# SparkFun_XBee3_Cat1_Smart_Modem.net
KiCad netlist of a schematic drawn in EAGLE
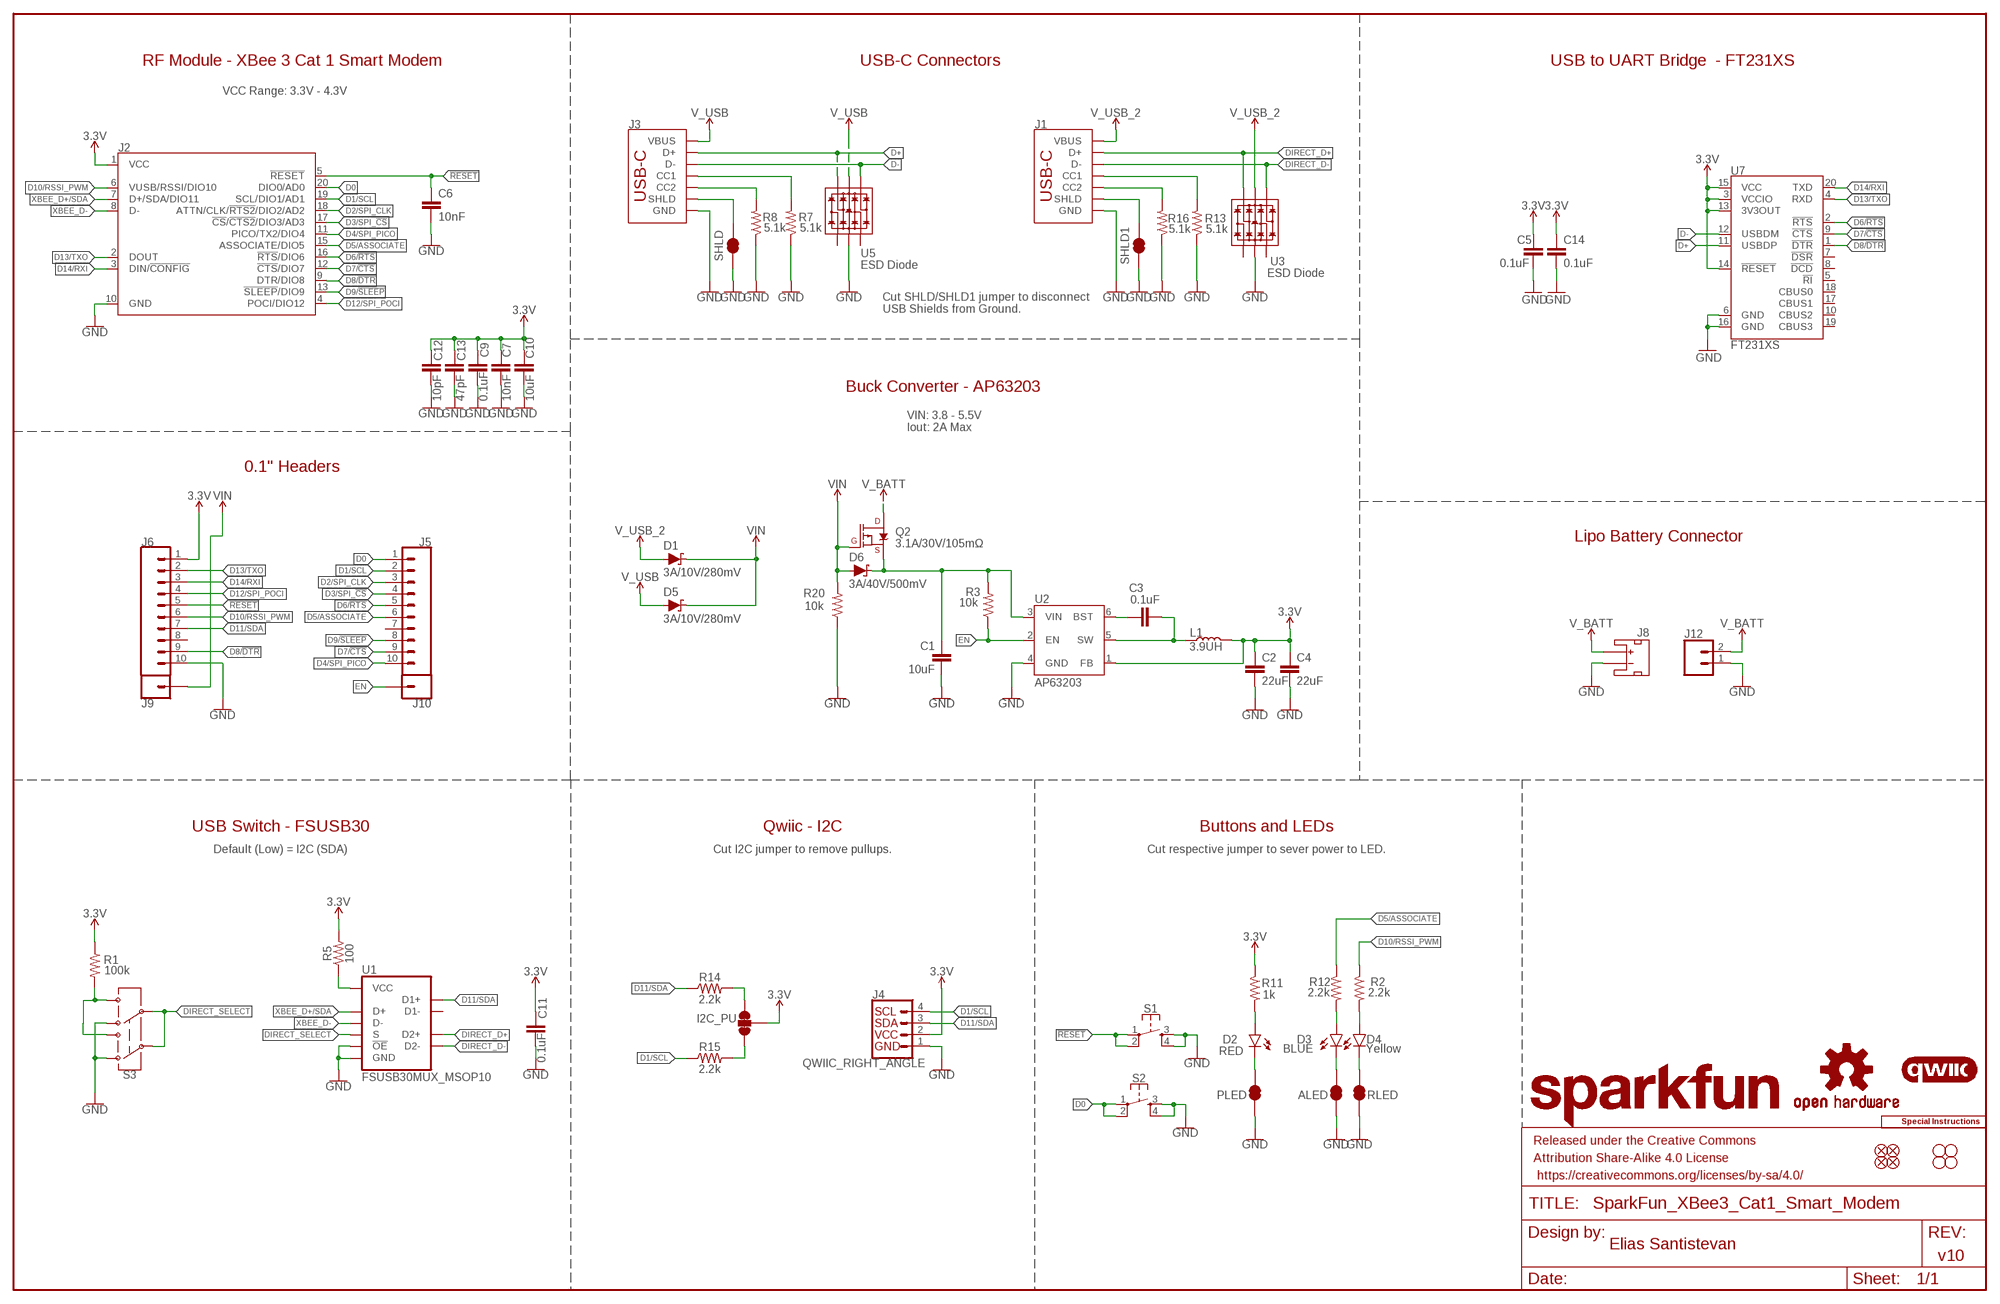
[diagram p0: schematic, sheet 1]

(export (version "E")
  (design (tool "Eeschema 10.0.6"))
  (components
    (comp (ref "ALED")
      (value "JUMPER-SMT_2_NC_TRACE_SILK")
      (footprint "eagle-import:SMT-JUMPER_2_NC_TRACE_SILK")
      (libsource (lib "eagle-import") (part "JUMPER-SMT_2_NC_TRACE_SILK"))
    )
    (comp (ref "C1")
      (value "10uF")
      (footprint "eagle-import:1210")
      (libsource (lib "eagle-import") (part "10UF-1210-50V-20%"))
    )
    (comp (ref "C2")
      (value "22uF")
      (footprint "eagle-import:0603")
      (libsource (lib "eagle-import") (part "22UF-0603-6.3V-20%"))
    )
    (comp (ref "C3")
      (value "0.1uF")
      (footprint "eagle-import:0603")
      (libsource (lib "eagle-import") (part "0.1UF-0603-25V-5%"))
    )
    (comp (ref "C4")
      (value "22uF")
      (footprint "eagle-import:0603")
      (libsource (lib "eagle-import") (part "22UF-0603-6.3V-20%"))
    )
    (comp (ref "C5")
      (value "0.1uF")
      (footprint "eagle-import:0603")
      (libsource (lib "eagle-import") (part "0.1UF-0603-25V-(+80/-20%)"))
    )
    (comp (ref "C6")
      (value "10nF")
      (footprint "eagle-import:0603")
      (libsource (lib "eagle-import") (part "10NF-0603-50V-10%"))
    )
    (comp (ref "C7")
      (value "10nF")
      (footprint "eagle-import:0603")
      (libsource (lib "eagle-import") (part "10NF-0603-50V-10%"))
    )
    (comp (ref "C9")
      (value "0.1uF")
      (footprint "eagle-import:0603")
      (libsource (lib "eagle-import") (part "0.1UF-0603-25V-(+80/-20%)"))
    )
    (comp (ref "C10")
      (value "10uF")
      (footprint "eagle-import:0603")
      (libsource (lib "eagle-import") (part "10UF-0603-6.3V-20%"))
    )
    (comp (ref "C11")
      (value "0.1uF")
      (footprint "eagle-import:0603")
      (libsource (lib "eagle-import") (part "0.1UF-0603-25V-(+80/-20%)"))
    )
    (comp (ref "C12")
      (value "10pF")
      (footprint "eagle-import:0603")
      (libsource (lib "eagle-import") (part "10PF-0603-50V-5%"))
    )
    (comp (ref "C13")
      (value "47pF")
      (footprint "eagle-import:0603")
      (libsource (lib "eagle-import") (part "47PF-0603-50V-5%"))
    )
    (comp (ref "C14")
      (value "0.1uF")
      (footprint "eagle-import:0603")
      (libsource (lib "eagle-import") (part "0.1UF-0603-25V-(+80/-20%)"))
    )
    (comp (ref "D1")
      (value "3A/10V/280mV")
      (footprint "eagle-import:SOD-323")
      (libsource (lib "eagle-import") (part "DIODE-SCHOTTKY-BAT60A"))
    )
    (comp (ref "D2")
      (value "RED")
      (footprint "eagle-import:LED-0603")
      (libsource (lib "eagle-import") (part "LED-RED0603"))
    )
    (comp (ref "D3")
      (value "BLUE")
      (footprint "eagle-import:LED-0603")
      (libsource (lib "eagle-import") (part "LED-BLUE0603"))
    )
    (comp (ref "D4")
      (value "Yellow")
      (footprint "eagle-import:LED-0603")
      (libsource (lib "eagle-import") (part "LED-YELLOW0603"))
    )
    (comp (ref "D5")
      (value "3A/10V/280mV")
      (footprint "eagle-import:SOD-323")
      (libsource (lib "eagle-import") (part "DIODE-SCHOTTKY-BAT60A"))
    )
    (comp (ref "D6")
      (value "3A/40V/500mV")
      (footprint "eagle-import:SMA-DIODE")
      (libsource (lib "eagle-import") (part "DIODE-SCHOTTKY-B340A"))
    )
    (comp (ref "FD1")
      (value "FIDUCIAL1X2")
      (footprint "eagle-import:FIDUCIAL-1X2")
      (libsource (lib "eagle-import") (part "FIDUCIAL1X2"))
    )
    (comp (ref "FD2")
      (value "FIDUCIAL1X2")
      (footprint "eagle-import:FIDUCIAL-1X2")
      (libsource (lib "eagle-import") (part "FIDUCIAL1X2"))
    )
    (comp (ref "FD3")
      (value "FIDUCIAL1X2")
      (footprint "eagle-import:FIDUCIAL-1X2")
      (libsource (lib "eagle-import") (part "FIDUCIAL1X2"))
    )
    (comp (ref "FD4")
      (value "FIDUCIAL1X2")
      (footprint "eagle-import:FIDUCIAL-1X2")
      (libsource (lib "eagle-import") (part "FIDUCIAL1X2"))
    )
    (comp (ref "FRAME1")
      (value "FRAME-LEDGER")
      (footprint "eagle-import:CREATIVE_COMMONS")
      (libsource (lib "eagle-import") (part "FRAME-LEDGER"))
    )
    (comp (ref "H1")
      (value "STAND-OFFTIGHT")
      (footprint "eagle-import:STAND-OFF-TIGHT")
      (libsource (lib "eagle-import") (part "STAND-OFFTIGHT"))
    )
    (comp (ref "H2")
      (value "STAND-OFFTIGHT")
      (footprint "eagle-import:STAND-OFF-TIGHT")
      (libsource (lib "eagle-import") (part "STAND-OFFTIGHT"))
    )
    (comp (ref "H3")
      (value "STAND-OFFTIGHT")
      (footprint "eagle-import:STAND-OFF-TIGHT")
      (libsource (lib "eagle-import") (part "STAND-OFFTIGHT"))
    )
    (comp (ref "H4")
      (value "STAND-OFFTIGHT")
      (footprint "eagle-import:STAND-OFF-TIGHT")
      (libsource (lib "eagle-import") (part "STAND-OFFTIGHT"))
    )
    (comp (ref "I2C_PU")
      (value "JUMPER-SMT_3_2-NC_TRACE_SILK")
      (footprint "eagle-import:SMT-JUMPER_3_2-NC_TRACE_SILK")
      (libsource (lib "eagle-import") (part "JUMPER-SMT_3_2-NC_TRACE_SILK"))
    )
    (comp (ref "J1")
      (value "USB Female Type C Connector")
      (footprint "eagle-import:USB-C-16P-4LAYER-ISOLATED")
      (libsource (lib "eagle-import") (part "USB_C_4-LAYER-ISOLATED"))
    )
    (comp (ref "J2")
      (value "XBEE_UPDATEXBEE_SMD")
      (footprint "eagle-import:XBEE3-SMD")
      (libsource (lib "eagle-import") (part "XBEE_UPDATEXBEE_SMD"))
    )
    (comp (ref "J3")
      (value "USB Female Type C Connector")
      (footprint "eagle-import:USB-C-16P-4LAYER-ISOLATED")
      (libsource (lib "eagle-import") (part "USB_C_4-LAYER-ISOLATED"))
    )
    (comp (ref "J4")
      (value "QWIIC_RIGHT_ANGLE")
      (footprint "eagle-import:JST04_1MM_RA")
      (libsource (lib "eagle-import") (part "QWIIC_CONNECTORJS-1MM"))
    )
    (comp (ref "J5")
      (value "CONN_10NO_SILK_PTH_FEMALE")
      (footprint "eagle-import:1X10_NO_SILK")
      (libsource (lib "eagle-import") (part "CONN_10NO_SILK_PTH_FEMALE"))
    )
    (comp (ref "J6")
      (value "CONN_10NO_SILK_PTH_FEMALE")
      (footprint "eagle-import:1X10_NO_SILK")
      (libsource (lib "eagle-import") (part "CONN_10NO_SILK_PTH_FEMALE"))
    )
    (comp (ref "J8")
      (value "JST_2MM_MALE")
      (footprint "eagle-import:JST-2-SMD")
      (libsource (lib "eagle-import") (part "JST_2MM_MALE"))
    )
    (comp (ref "J9")
      (value "CONN_01PTH_NO_SILK_STAND")
      (footprint "eagle-import:1X01_NO_SILK_STAND")
      (libsource (lib "eagle-import") (part "CONN_01PTH_NO_SILK_STAND"))
    )
    (comp (ref "J10")
      (value "CONN_01PTH_NO_SILK_STAND")
      (footprint "eagle-import:1X01_NO_SILK_STAND")
      (libsource (lib "eagle-import") (part "CONN_01PTH_NO_SILK_STAND"))
    )
    (comp (ref "J12")
      (value "CONN_021X02_NO_SILK")
      (footprint "eagle-import:1X02_NO_SILK")
      (libsource (lib "eagle-import") (part "CONN_021X02_NO_SILK"))
    )
    (comp (ref "L1")
      (value "3.9UH")
      (footprint "eagle-import:INDUCTOR_3.9UH")
      (libsource (lib "eagle-import") (part "3.9UH"))
    )
    (comp (ref "LOGO1")
      (value "SFE_LOGO_NAME.2_INCH")
      (footprint "eagle-import:SFE_LOGO_NAME_.2")
      (libsource (lib "eagle-import") (part "SFE_LOGO_NAME.2_INCH"))
    )
    (comp (ref "LOGO2")
      (value "OSHW-LOGOS")
      (footprint "eagle-import:OSHW-LOGO-S")
      (libsource (lib "eagle-import") (part "OSHW-LOGOS"))
    )
    (comp (ref "LOGO3")
      (value "QWIIC_LOGO_5MM")
      (footprint "eagle-import:QWIIC_5MM")
      (libsource (lib "eagle-import") (part "QWIIC_LOGO_5MM"))
    )
    (comp (ref "LOGO5")
      (value "SPECIAL_INSTRUCTIONS-ORDERING")
      (footprint "eagle-import:ORDERING_INSTRUCTIONS")
      (libsource (lib "eagle-import") (part "SPECIAL_INSTRUCTIONS-ORDERING"))
    )
    (comp (ref "PLED")
      (value "JUMPER-SMT_2_NC_TRACE_SILK")
      (footprint "eagle-import:SMT-JUMPER_2_NC_TRACE_SILK")
      (libsource (lib "eagle-import") (part "JUMPER-SMT_2_NC_TRACE_SILK"))
    )
    (comp (ref "Q2")
      (value "3.1A/30V/105mΩ")
      (footprint "eagle-import:SOT23-3")
      (libsource (lib "eagle-import") (part "MOSFET_PCH-DMG2307L"))
    )
    (comp (ref "R1")
      (value "100k")
      (footprint "eagle-import:0603")
      (libsource (lib "eagle-import") (part "100KOHM-0603-1/10W-1%"))
    )
    (comp (ref "R2")
      (value "2.2k")
      (footprint "eagle-import:0603")
      (libsource (lib "eagle-import") (part "2.2KOHM-0603-1/10W-1%"))
    )
    (comp (ref "R3")
      (value "10k")
      (footprint "eagle-import:0603")
      (libsource (lib "eagle-import") (part "10KOHM-0603-1/10W-1%"))
    )
    (comp (ref "R5")
      (value "100")
      (footprint "eagle-import:0603")
      (libsource (lib "eagle-import") (part "100OHM-0603-1/10W-1%"))
    )
    (comp (ref "R7")
      (value "5.1k")
      (footprint "eagle-import:0603")
      (libsource (lib "eagle-import") (part "5.1KOHM5.1KOHM-0603-1/10W-1%"))
    )
    (comp (ref "R8")
      (value "5.1k")
      (footprint "eagle-import:0603")
      (libsource (lib "eagle-import") (part "5.1KOHM5.1KOHM-0603-1/10W-1%"))
    )
    (comp (ref "R11")
      (value "1k")
      (footprint "eagle-import:0603")
      (libsource (lib "eagle-import") (part "1KOHM-0603-1/10W-1%"))
    )
    (comp (ref "R12")
      (value "2.2k")
      (footprint "eagle-import:0603")
      (libsource (lib "eagle-import") (part "2.2KOHM-0603-1/10W-1%"))
    )
    (comp (ref "R13")
      (value "5.1k")
      (footprint "eagle-import:0603")
      (libsource (lib "eagle-import") (part "5.1KOHM5.1KOHM-0603-1/10W-1%"))
    )
    (comp (ref "R14")
      (value "2.2k")
      (footprint "eagle-import:0603")
      (libsource (lib "eagle-import") (part "2.2KOHM-0603-1/10W-1%"))
    )
    (comp (ref "R15")
      (value "2.2k")
      (footprint "eagle-import:0603")
      (libsource (lib "eagle-import") (part "2.2KOHM-0603-1/10W-1%"))
    )
    (comp (ref "R16")
      (value "5.1k")
      (footprint "eagle-import:0603")
      (libsource (lib "eagle-import") (part "5.1KOHM5.1KOHM-0603-1/10W-1%"))
    )
    (comp (ref "R20")
      (value "10k")
      (footprint "eagle-import:0603")
      (libsource (lib "eagle-import") (part "10KOHM-0603-1/10W-1%"))
    )
    (comp (ref "RLED")
      (value "JUMPER-SMT_2_NC_TRACE_SILK")
      (footprint "eagle-import:SMT-JUMPER_2_NC_TRACE_SILK")
      (libsource (lib "eagle-import") (part "JUMPER-SMT_2_NC_TRACE_SILK"))
    )
    (comp (ref "S1")
      (value "MOMENTARY-SWITCH-SPST-2-SMD-5.2MM-TALL")
      (footprint "eagle-import:TACTILE_SWITCH_SMD_5.2MM")
      (libsource (lib "eagle-import") (part "MOMENTARY-SWITCH-SPST-2-SMD-5.2MM-TALL"))
    )
    (comp (ref "S2")
      (value "MOMENTARY-SWITCH-SPST-2-SMD-5.2MM-TALL")
      (footprint "eagle-import:TACTILE_SWITCH_SMD_5.2MM")
      (libsource (lib "eagle-import") (part "MOMENTARY-SWITCH-SPST-2-SMD-5.2MM-TALL"))
    )
    (comp (ref "S3")
      (value "SWITCH-DPDT-SMD-AYZ0202")
      (footprint "eagle-import:SWITCH_DPDT_SMD_AYZ0202")
      (libsource (lib "eagle-import") (part "SWITCH-DPDT-SMD-AYZ0202"))
    )
    (comp (ref "SHLD")
      (value "JUMPER-SMT_2_NC_TRACE_SILK")
      (footprint "eagle-import:SMT-JUMPER_2_NC_TRACE_SILK")
      (libsource (lib "eagle-import") (part "JUMPER-SMT_2_NC_TRACE_SILK"))
    )
    (comp (ref "SHLD1")
      (value "JUMPER-SMT_2_NC_TRACE_SILK")
      (footprint "eagle-import:SMT-JUMPER_2_NC_TRACE_SILK")
      (libsource (lib "eagle-import") (part "JUMPER-SMT_2_NC_TRACE_SILK"))
    )
    (comp (ref "U1")
      (value "FSUSB30MUX_MSOP10")
      (footprint "eagle-import:MSOP10")
      (libsource (lib "eagle-import") (part "FSUSB30MUX_MSOP10"))
    )
    (comp (ref "U2")
      (value "AP63203")
      (footprint "eagle-import:SOT23-6")
      (libsource (lib "eagle-import") (part "AP63203"))
    )
    (comp (ref "U3")
      (value "ESD Diode")
      (footprint "eagle-import:SOT-23-6")
      (libsource (lib "eagle-import") (part "TVS_DIODE_ARRAY_DT1042-04SO-7"))
    )
    (comp (ref "U5")
      (value "ESD Diode")
      (footprint "eagle-import:SOT-23-6")
      (libsource (lib "eagle-import") (part "TVS_DIODE_ARRAY_DT1042-04SO-7"))
    )
    (comp (ref "U7")
      (value "FT231XS")
      (footprint "eagle-import:SSOP20_L")
      (libsource (lib "eagle-import") (part "FT231XS"))
    )
  )
  (nets
    (net (code "1") (name "/D3{slash}SPI_~{CS}") (class "Default")
      (node (ref "J2") (pin "17") (pinfunction "~{CS}/~{CTS2}/DIO3/AD3_17") (pintype "bidirectional"))
      (node (ref "J5") (pin "4") (pinfunction "4_4") (pintype "passive"))
    )
    (net (code "2") (name "/D6{slash}~{RTS}") (class "Default")
      (node (ref "J2") (pin "16") (pinfunction "~{RTS}/DIO6_16") (pintype "input"))
      (node (ref "J5") (pin "5") (pinfunction "5_5") (pintype "passive"))
      (node (ref "U7") (pin "2") (pinfunction "~{RTS}_2") (pintype "bidirectional"))
    )
    (net (code "3") (name "/D7{slash}~{CTS}") (class "Default")
      (node (ref "J2") (pin "12") (pinfunction "~{CTS}/DIO7_12") (pintype "output"))
      (node (ref "J5") (pin "9") (pinfunction "9_9") (pintype "passive"))
      (node (ref "U7") (pin "9") (pinfunction "~{CTS}_9") (pintype "bidirectional"))
    )
    (net (code "4") (name "/D8{slash}~{DTR}") (class "Default")
      (node (ref "J2") (pin "9") (pinfunction "DTR/DIO8_9") (pintype "bidirectional"))
      (node (ref "J6") (pin "9") (pinfunction "9_9") (pintype "passive"))
      (node (ref "U7") (pin "1") (pinfunction "~{DTR}_1") (pintype "bidirectional"))
    )
    (net (code "5") (name "/D9{slash}~{SLEEP}") (class "Default")
      (node (ref "J2") (pin "13") (pinfunction "~{SLEEP}/DIO9_13") (pintype "bidirectional"))
      (node (ref "J5") (pin "8") (pinfunction "8_8") (pintype "passive"))
    )
    (net (code "6") (name "/~{RESET}") (class "Default")
      (node (ref "C6") (pin "1") (pinfunction "1_1") (pintype "passive"))
      (node (ref "J2") (pin "5") (pinfunction "~{RESET}_5") (pintype "input"))
      (node (ref "J6") (pin "5") (pinfunction "5_5") (pintype "passive"))
      (node (ref "S1") (pin "1") (pinfunction "1_1") (pintype "passive"))
      (node (ref "S1") (pin "2") (pinfunction "2_2") (pintype "passive"))
    )
    (net (code "7") (name "3.3V") (class "Default")
      (node (ref "C10") (pin "1") (pinfunction "1_1") (pintype "passive"))
      (node (ref "C11") (pin "1") (pinfunction "1_1") (pintype "passive"))
      (node (ref "C12") (pin "1") (pinfunction "1_1") (pintype "passive"))
      (node (ref "C13") (pin "1") (pinfunction "1_1") (pintype "passive"))
      (node (ref "C14") (pin "1") (pinfunction "1_1") (pintype "passive"))
      (node (ref "C2") (pin "1") (pinfunction "1_1") (pintype "passive"))
      (node (ref "C4") (pin "1") (pinfunction "1_1") (pintype "passive"))
      (node (ref "C5") (pin "1") (pinfunction "1_1") (pintype "passive"))
      (node (ref "C7") (pin "1") (pinfunction "1_1") (pintype "passive"))
      (node (ref "C9") (pin "1") (pinfunction "1_1") (pintype "passive"))
      (node (ref "I2C_PU") (pin "2") (pinfunction "2_2") (pintype "passive"))
      (node (ref "J2") (pin "1") (pinfunction "VCC_1") (pintype "power_in"))
      (node (ref "J4") (pin "2") (pinfunction "2_2") (pintype "power_in"))
      (node (ref "J6") (pin "1") (pinfunction "1_1") (pintype "passive"))
      (node (ref "L1") (pin "P$2") (pinfunction "2_P$2") (pintype "passive"))
      (node (ref "R1") (pin "1") (pinfunction "1_1") (pintype "passive"))
      (node (ref "R11") (pin "1") (pinfunction "1_1") (pintype "passive"))
      (node (ref "R5") (pin "2") (pinfunction "2_2") (pintype "passive"))
      (node (ref "U2") (pin "1") (pinfunction "FB_1") (pintype "bidirectional"))
      (node (ref "U7") (pin "13") (pinfunction "3V3OUT_13") (pintype "bidirectional"))
      (node (ref "U7") (pin "14") (pinfunction "~{RESET}_14") (pintype "bidirectional"))
      (node (ref "U7") (pin "15") (pinfunction "VCC_15") (pintype "bidirectional"))
      (node (ref "U7") (pin "3") (pinfunction "VCCIO_3") (pintype "bidirectional"))
    )
    (net (code "8") (name "D+") (class "Default")
      (node (ref "J3") (pin "A6") (pinfunction "D+_A6") (pintype "bidirectional"))
      (node (ref "J3") (pin "B6") (pinfunction "D+_B6") (pintype "bidirectional"))
      (node (ref "U5") (pin "6") (pinfunction "IO4_6") (pintype "bidirectional"))
      (node (ref "U7") (pin "11") (pinfunction "USBDP_11") (pintype "bidirectional"))
    )
    (net (code "9") (name "D-") (class "Default")
      (node (ref "J3") (pin "A7") (pinfunction "D-_A7") (pintype "bidirectional"))
      (node (ref "J3") (pin "B7") (pinfunction "D-_B7") (pintype "bidirectional"))
      (node (ref "U5") (pin "4") (pinfunction "IO3_4") (pintype "bidirectional"))
      (node (ref "U7") (pin "12") (pinfunction "USBDM_12") (pintype "bidirectional"))
    )
    (net (code "10") (name "D0") (class "Default")
      (node (ref "J2") (pin "20") (pinfunction "DIO0/AD0_20") (pintype "bidirectional"))
      (node (ref "J5") (pin "1") (pinfunction "1_1") (pintype "passive"))
      (node (ref "S2") (pin "1") (pinfunction "1_1") (pintype "passive"))
      (node (ref "S2") (pin "2") (pinfunction "2_2") (pintype "passive"))
    )
    (net (code "11") (name "D1{slash}SCL") (class "Default")
      (node (ref "J2") (pin "19") (pinfunction "SCL/DIO1/AD1_19") (pintype "bidirectional"))
      (node (ref "J4") (pin "4") (pinfunction "4_4") (pintype "passive"))
      (node (ref "J5") (pin "2") (pinfunction "2_2") (pintype "passive"))
      (node (ref "R15") (pin "1") (pinfunction "1_1") (pintype "passive"))
    )
    (net (code "12") (name "D2{slash}SPI_CLK") (class "Default")
      (node (ref "J2") (pin "18") (pinfunction "ATTN/CLK/~{RTS2}/DIO2/AD2_18") (pintype "bidirectional"))
      (node (ref "J5") (pin "3") (pinfunction "3_3") (pintype "passive"))
    )
    (net (code "13") (name "D4{slash}SPI_PICO") (class "Default")
      (node (ref "J2") (pin "11") (pinfunction "PICO/TX2/DIO4_11") (pintype "bidirectional"))
      (node (ref "J5") (pin "10") (pinfunction "10_10") (pintype "passive"))
    )
    (net (code "14") (name "D5{slash}ASSOCIATE") (class "Default")
      (node (ref "J2") (pin "15") (pinfunction "ASSOCIATE/DIO5_15") (pintype "bidirectional"))
      (node (ref "J5") (pin "6") (pinfunction "6_6") (pintype "passive"))
      (node (ref "R12") (pin "1") (pinfunction "1_1") (pintype "passive"))
    )
    (net (code "15") (name "D10{slash}RSSI_PWM") (class "Default")
      (node (ref "J2") (pin "6") (pinfunction "VUSB/RSSI/DIO10_6") (pintype "bidirectional"))
      (node (ref "J6") (pin "6") (pinfunction "6_6") (pintype "passive"))
      (node (ref "R2") (pin "1") (pinfunction "1_1") (pintype "passive"))
    )
    (net (code "16") (name "D11{slash}SDA") (class "Default")
      (node (ref "J4") (pin "3") (pinfunction "3_3") (pintype "passive"))
      (node (ref "J6") (pin "7") (pinfunction "7_7") (pintype "passive"))
      (node (ref "R14") (pin "1") (pinfunction "1_1") (pintype "passive"))
      (node (ref "U1") (pin "2") (pinfunction "D1+_2") (pintype "bidirectional"))
    )
    (net (code "17") (name "D12{slash}SPI_POCI") (class "Default")
      (node (ref "J2") (pin "4") (pinfunction "POCI/DIO12_4") (pintype "bidirectional"))
      (node (ref "J6") (pin "4") (pinfunction "4_4") (pintype "passive"))
    )
    (net (code "18") (name "D13{slash}TXO") (class "Default")
      (node (ref "J2") (pin "2") (pinfunction "DOUT_2") (pintype "output"))
      (node (ref "J6") (pin "2") (pinfunction "2_2") (pintype "passive"))
      (node (ref "U7") (pin "4") (pinfunction "RXD_4") (pintype "bidirectional"))
    )
    (net (code "19") (name "D14{slash}RXI") (class "Default")
      (node (ref "J2") (pin "3") (pinfunction "DIN/~{CONFIG}_3") (pintype "input"))
      (node (ref "J6") (pin "3") (pinfunction "3_3") (pintype "passive"))
      (node (ref "U7") (pin "20") (pinfunction "TXD_20") (pintype "bidirectional"))
    )
    (net (code "20") (name "DIRECT_D+") (class "Default")
      (node (ref "J1") (pin "A6") (pinfunction "D+_A6") (pintype "bidirectional"))
      (node (ref "J1") (pin "B6") (pinfunction "D+_B6") (pintype "bidirectional"))
      (node (ref "U1") (pin "3") (pinfunction "D2+_3") (pintype "bidirectional"))
      (node (ref "U3") (pin "6") (pinfunction "IO4_6") (pintype "bidirectional"))
    )
    (net (code "21") (name "DIRECT_D-") (class "Default")
      (node (ref "J1") (pin "A7") (pinfunction "D-_A7") (pintype "bidirectional"))
      (node (ref "J1") (pin "B7") (pinfunction "D-_B7") (pintype "bidirectional"))
      (node (ref "U1") (pin "7") (pinfunction "D2-_7") (pintype "bidirectional"))
      (node (ref "U3") (pin "4") (pinfunction "IO3_4") (pintype "bidirectional"))
    )
    (net (code "22") (name "DIRECT_SELECT") (class "Default")
      (node (ref "S3") (pin "2") (pinfunction "2_2") (pintype "bidirectional"))
      (node (ref "S3") (pin "5") (pinfunction "5_5") (pintype "bidirectional"))
      (node (ref "U1") (pin "1") (pinfunction "S_1") (pintype "bidirectional"))
    )
    (net (code "23") (name "EN") (class "Default")
      (node (ref "J10") (pin "1") (pinfunction "1_1") (pintype "passive"))
      (node (ref "R3") (pin "1") (pinfunction "1_1") (pintype "passive"))
      (node (ref "U2") (pin "2") (pinfunction "EN_2") (pintype "bidirectional"))
    )
    (net (code "24") (name "GND") (class "Default")
      (node (ref "ALED") (pin "1") (pinfunction "1_1") (pintype "passive"))
      (node (ref "C1") (pin "2") (pinfunction "2_2") (pintype "passive"))
      (node (ref "C10") (pin "2") (pinfunction "2_2") (pintype "passive"))
      (node (ref "C11") (pin "2") (pinfunction "2_2") (pintype "passive"))
      (node (ref "C12") (pin "2") (pinfunction "2_2") (pintype "passive"))
      (node (ref "C13") (pin "2") (pinfunction "2_2") (pintype "passive"))
      (node (ref "C14") (pin "2") (pinfunction "2_2") (pintype "passive"))
      (node (ref "C2") (pin "2") (pinfunction "2_2") (pintype "passive"))
      (node (ref "C4") (pin "2") (pinfunction "2_2") (pintype "passive"))
      (node (ref "C5") (pin "2") (pinfunction "2_2") (pintype "passive"))
      (node (ref "C6") (pin "2") (pinfunction "2_2") (pintype "passive"))
      (node (ref "C7") (pin "2") (pinfunction "2_2") (pintype "passive"))
      (node (ref "C9") (pin "2") (pinfunction "2_2") (pintype "passive"))
      (node (ref "J1") (pin "GND") (pinfunction "GND_GND") (pintype "bidirectional"))
      (node (ref "J1") (pin "GND2") (pinfunction "GND_GND2") (pintype "bidirectional"))
      (node (ref "J12") (pin "1") (pinfunction "1_1") (pintype "passive"))
      (node (ref "J2") (pin "10") (pinfunction "GND_10") (pintype "power_in"))
      (node (ref "J3") (pin "GND") (pinfunction "GND_GND") (pintype "bidirectional"))
      (node (ref "J3") (pin "GND2") (pinfunction "GND_GND2") (pintype "bidirectional"))
      (node (ref "J4") (pin "1") (pinfunction "1_1") (pintype "power_in"))
      (node (ref "J6") (pin "10") (pinfunction "10_10") (pintype "passive"))
      (node (ref "J8") (pin "1") (pinfunction "-_1") (pintype "bidirectional"))
      (node (ref "PLED") (pin "1") (pinfunction "1_1") (pintype "passive"))
      (node (ref "R13") (pin "1") (pinfunction "1_1") (pintype "passive"))
      (node (ref "R16") (pin "1") (pinfunction "1_1") (pintype "passive"))
      (node (ref "R20") (pin "1") (pinfunction "1_1") (pintype "passive"))
      (node (ref "R7") (pin "1") (pinfunction "1_1") (pintype "passive"))
      (node (ref "R8") (pin "1") (pinfunction "1_1") (pintype "passive"))
      (node (ref "RLED") (pin "1") (pinfunction "1_1") (pintype "passive"))
      (node (ref "S1") (pin "3") (pinfunction "3_3") (pintype "passive"))
      (node (ref "S1") (pin "4") (pinfunction "4_4") (pintype "passive"))
      (node (ref "S2") (pin "3") (pinfunction "3_3") (pintype "passive"))
      (node (ref "S2") (pin "4") (pinfunction "4_4") (pintype "passive"))
      (node (ref "S3") (pin "3") (pinfunction "3_3") (pintype "bidirectional"))
      (node (ref "S3") (pin "6") (pinfunction "6_6") (pintype "bidirectional"))
      (node (ref "SHLD") (pin "1") (pinfunction "1_1") (pintype "passive"))
      (node (ref "SHLD1") (pin "1") (pinfunction "1_1") (pintype "passive"))
      (node (ref "U1") (pin "5") (pinfunction "GND_5") (pintype "bidirectional"))
      (node (ref "U1") (pin "9") (pinfunction "~{OE}_9") (pintype "bidirectional"))
      (node (ref "U2") (pin "4") (pinfunction "GND_4") (pintype "bidirectional"))
      (node (ref "U3") (pin "2") (pinfunction "VSS_2") (pintype "bidirectional"))
      (node (ref "U5") (pin "2") (pinfunction "VSS_2") (pintype "bidirectional"))
      (node (ref "U7") (pin "16") (pinfunction "GND_16") (pintype "bidirectional"))
      (node (ref "U7") (pin "6") (pinfunction "GND_6") (pintype "bidirectional"))
    )
    (net (code "25") (name "Net-(ALED-Pad2)") (class "Default")
      (node (ref "ALED") (pin "2") (pinfunction "2_2") (pintype "passive"))
      (node (ref "D3") (pin "C") (pinfunction "C_C") (pintype "passive"))
    )
    (net (code "26") (name "Net-(D2-PadA)") (class "Default")
      (node (ref "D2") (pin "A") (pinfunction "A_A") (pintype "passive"))
      (node (ref "R11") (pin "2") (pinfunction "2_2") (pintype "passive"))
    )
    (net (code "27") (name "Net-(D2-PadC)") (class "Default")
      (node (ref "D2") (pin "C") (pinfunction "C_C") (pintype "passive"))
      (node (ref "PLED") (pin "2") (pinfunction "2_2") (pintype "passive"))
    )
    (net (code "28") (name "Net-(D3-PadA)") (class "Default")
      (node (ref "D3") (pin "A") (pinfunction "A_A") (pintype "passive"))
      (node (ref "R12") (pin "2") (pinfunction "2_2") (pintype "passive"))
    )
    (net (code "29") (name "Net-(D4-PadA)") (class "Default")
      (node (ref "D4") (pin "A") (pinfunction "A_A") (pintype "passive"))
      (node (ref "R2") (pin "2") (pinfunction "2_2") (pintype "passive"))
    )
    (net (code "30") (name "Net-(D4-PadC)") (class "Default")
      (node (ref "D4") (pin "C") (pinfunction "C_C") (pintype "passive"))
      (node (ref "RLED") (pin "2") (pinfunction "2_2") (pintype "passive"))
    )
    (net (code "31") (name "Net-(I2C_PU-Pad1)") (class "Default")
      (node (ref "I2C_PU") (pin "1") (pinfunction "1_1") (pintype "passive"))
      (node (ref "R15") (pin "2") (pinfunction "2_2") (pintype "passive"))
    )
    (net (code "32") (name "Net-(I2C_PU-Pad3)") (class "Default")
      (node (ref "I2C_PU") (pin "3") (pinfunction "3_3") (pintype "passive"))
      (node (ref "R14") (pin "2") (pinfunction "2_2") (pintype "passive"))
    )
    (net (code "33") (name "Net-(J1-CC1)") (class "Default")
      (node (ref "J1") (pin "A5") (pinfunction "CC1_A5") (pintype "bidirectional"))
      (node (ref "R13") (pin "2") (pinfunction "2_2") (pintype "passive"))
    )
    (net (code "34") (name "Net-(J1-CC2)") (class "Default")
      (node (ref "J1") (pin "B5") (pinfunction "CC2_B5") (pintype "bidirectional"))
      (node (ref "R16") (pin "2") (pinfunction "2_2") (pintype "passive"))
    )
    (net (code "35") (name "Net-(J1-SHLD-PadSHLD1)") (class "Default")
      (node (ref "J1") (pin "SHLD1") (pinfunction "SHLD_SHLD1") (pintype "bidirectional"))
      (node (ref "J1") (pin "SHLD2") (pinfunction "SHLD_SHLD2") (pintype "bidirectional"))
      (node (ref "J1") (pin "SHLD3") (pinfunction "SHLD_SHLD3") (pintype "bidirectional"))
      (node (ref "J1") (pin "SHLD4") (pinfunction "SHLD_SHLD4") (pintype "bidirectional"))
      (node (ref "J1") (pin "SHLD5") (pinfunction "SHLD_SHLD5") (pintype "bidirectional"))
      (node (ref "J1") (pin "SHLD6") (pinfunction "SHLD_SHLD6") (pintype "bidirectional"))
      (node (ref "J1") (pin "SHLD7") (pinfunction "SHLD_SHLD7") (pintype "bidirectional"))
      (node (ref "J1") (pin "SHLD8") (pinfunction "SHLD_SHLD8") (pintype "bidirectional"))
      (node (ref "SHLD1") (pin "2") (pinfunction "2_2") (pintype "passive"))
    )
    (net (code "36") (name "Net-(J3-CC1)") (class "Default")
      (node (ref "J3") (pin "A5") (pinfunction "CC1_A5") (pintype "bidirectional"))
      (node (ref "R7") (pin "2") (pinfunction "2_2") (pintype "passive"))
    )
    (net (code "37") (name "Net-(J3-CC2)") (class "Default")
      (node (ref "J3") (pin "B5") (pinfunction "CC2_B5") (pintype "bidirectional"))
      (node (ref "R8") (pin "2") (pinfunction "2_2") (pintype "passive"))
    )
    (net (code "38") (name "Net-(J3-SHLD-PadSHLD1)") (class "Default")
      (node (ref "J3") (pin "SHLD1") (pinfunction "SHLD_SHLD1") (pintype "bidirectional"))
      (node (ref "J3") (pin "SHLD2") (pinfunction "SHLD_SHLD2") (pintype "bidirectional"))
      (node (ref "J3") (pin "SHLD3") (pinfunction "SHLD_SHLD3") (pintype "bidirectional"))
      (node (ref "J3") (pin "SHLD4") (pinfunction "SHLD_SHLD4") (pintype "bidirectional"))
      (node (ref "J3") (pin "SHLD5") (pinfunction "SHLD_SHLD5") (pintype "bidirectional"))
      (node (ref "J3") (pin "SHLD6") (pinfunction "SHLD_SHLD6") (pintype "bidirectional"))
      (node (ref "J3") (pin "SHLD7") (pinfunction "SHLD_SHLD7") (pintype "bidirectional"))
      (node (ref "J3") (pin "SHLD8") (pinfunction "SHLD_SHLD8") (pintype "bidirectional"))
      (node (ref "SHLD") (pin "2") (pinfunction "2_2") (pintype "passive"))
    )
    (net (code "39") (name "Net-(L1-1)") (class "Default")
      (node (ref "C3") (pin "2") (pinfunction "2_2") (pintype "passive"))
      (node (ref "L1") (pin "P$1") (pinfunction "1_P$1") (pintype "passive"))
      (node (ref "U2") (pin "5") (pinfunction "SW_5") (pintype "bidirectional"))
    )
    (net (code "40") (name "Net-(Q2-S)") (class "Default")
      (node (ref "C1") (pin "1") (pinfunction "1_1") (pintype "passive"))
      (node (ref "D6") (pin "C") (pinfunction "C_C") (pintype "passive"))
      (node (ref "Q2") (pin "2") (pinfunction "S_2") (pintype "bidirectional"))
      (node (ref "R3") (pin "2") (pinfunction "2_2") (pintype "passive"))
      (node (ref "U2") (pin "3") (pinfunction "VIN_3") (pintype "bidirectional"))
    )
    (net (code "41") (name "Net-(R1-Pad2)") (class "Default")
      (node (ref "R1") (pin "2") (pinfunction "2_2") (pintype "passive"))
      (node (ref "S3") (pin "1") (pinfunction "1_1") (pintype "bidirectional"))
      (node (ref "S3") (pin "4") (pinfunction "4_4") (pintype "bidirectional"))
    )
    (net (code "42") (name "Net-(U1-VCC)") (class "Default")
      (node (ref "R5") (pin "1") (pinfunction "1_1") (pintype "passive"))
      (node (ref "U1") (pin "10") (pinfunction "VCC_10") (pintype "bidirectional"))
    )
    (net (code "43") (name "Net-(U2-BST)") (class "Default")
      (node (ref "C3") (pin "1") (pinfunction "1_1") (pintype "passive"))
      (node (ref "U2") (pin "6") (pinfunction "BST_6") (pintype "bidirectional"))
    )
    (net (code "44") (name "VIN") (class "Default")
      (node (ref "D1") (pin "C") (pinfunction "C_C") (pintype "passive"))
      (node (ref "D5") (pin "C") (pinfunction "C_C") (pintype "passive"))
      (node (ref "D6") (pin "A") (pinfunction "A_A") (pintype "passive"))
      (node (ref "J9") (pin "1") (pinfunction "1_1") (pintype "passive"))
      (node (ref "Q2") (pin "1") (pinfunction "G_1") (pintype "bidirectional"))
      (node (ref "R20") (pin "2") (pinfunction "2_2") (pintype "passive"))
    )
    (net (code "45") (name "V_BATT") (class "Default")
      (node (ref "J12") (pin "2") (pinfunction "2_2") (pintype "passive"))
      (node (ref "J8") (pin "2") (pinfunction "+_2") (pintype "bidirectional"))
      (node (ref "Q2") (pin "3") (pinfunction "D_3") (pintype "bidirectional"))
    )
    (net (code "46") (name "V_USB") (class "Default")
      (node (ref "D5") (pin "A") (pinfunction "A_A") (pintype "passive"))
      (node (ref "J3") (pin "VBUS1") (pinfunction "VBUS_VBUS1") (pintype "bidirectional"))
      (node (ref "J3") (pin "VBUS2") (pinfunction "VBUS_VBUS2") (pintype "bidirectional"))
      (node (ref "U5") (pin "5") (pinfunction "VCC_5") (pintype "bidirectional"))
    )
    (net (code "47") (name "V_USB_2") (class "Default")
      (node (ref "D1") (pin "A") (pinfunction "A_A") (pintype "passive"))
      (node (ref "J1") (pin "VBUS1") (pinfunction "VBUS_VBUS1") (pintype "bidirectional"))
      (node (ref "J1") (pin "VBUS2") (pinfunction "VBUS_VBUS2") (pintype "bidirectional"))
      (node (ref "U3") (pin "5") (pinfunction "VCC_5") (pintype "bidirectional"))
    )
    (net (code "48") (name "XBEE_D+{slash}SDA") (class "Default")
      (node (ref "J2") (pin "7") (pinfunction "D+/SDA/DIO11_7") (pintype "bidirectional"))
      (node (ref "U1") (pin "4") (pinfunction "D+_4") (pintype "bidirectional"))
    )
    (net (code "49") (name "XBEE_D-") (class "Default")
      (node (ref "J2") (pin "8") (pinfunction "D-_8") (pintype "bidirectional"))
      (node (ref "U1") (pin "6") (pinfunction "D-_6") (pintype "bidirectional"))
    )
    (net (code "50") (name "unconnected-(J5-Pad7)") (class "Default")
      (node (ref "J5") (pin "7") (pinfunction "7_7") (pintype "passive"))
    )
    (net (code "51") (name "unconnected-(J6-Pad8)") (class "Default")
      (node (ref "J6") (pin "8") (pinfunction "8_8") (pintype "passive"))
    )
    (net (code "52") (name "unconnected-(J8-PAD1-PadNC1)") (class "Default")
      (node (ref "J8") (pin "NC1") (pinfunction "PAD1_NC1") (pintype "bidirectional"))
    )
    (net (code "53") (name "unconnected-(J8-PAD2-PadNC2)") (class "Default")
      (node (ref "J8") (pin "NC2") (pinfunction "PAD2_NC2") (pintype "bidirectional"))
    )
    (net (code "54") (name "unconnected-(U1-D1--Pad8)") (class "Default")
      (node (ref "U1") (pin "8") (pinfunction "D1-_8") (pintype "bidirectional"))
    )
    (net (code "55") (name "unconnected-(U3-IO1-Pad1)") (class "Default")
      (node (ref "U3") (pin "1") (pinfunction "IO1_1") (pintype "bidirectional"))
    )
    (net (code "56") (name "unconnected-(U3-IO2-Pad3)") (class "Default")
      (node (ref "U3") (pin "3") (pinfunction "IO2_3") (pintype "bidirectional"))
    )
    (net (code "57") (name "unconnected-(U5-IO1-Pad1)") (class "Default")
      (node (ref "U5") (pin "1") (pinfunction "IO1_1") (pintype "bidirectional"))
    )
    (net (code "58") (name "unconnected-(U5-IO2-Pad3)") (class "Default")
      (node (ref "U5") (pin "3") (pinfunction "IO2_3") (pintype "bidirectional"))
    )
    (net (code "59") (name "unconnected-(U7-CBUS0-Pad18)") (class "Default")
      (node (ref "U7") (pin "18") (pinfunction "CBUS0_18") (pintype "bidirectional"))
    )
    (net (code "60") (name "unconnected-(U7-CBUS1-Pad17)") (class "Default")
      (node (ref "U7") (pin "17") (pinfunction "CBUS1_17") (pintype "bidirectional"))
    )
    (net (code "61") (name "unconnected-(U7-CBUS2-Pad10)") (class "Default")
      (node (ref "U7") (pin "10") (pinfunction "CBUS2_10") (pintype "bidirectional"))
    )
    (net (code "62") (name "unconnected-(U7-CBUS3-Pad19)") (class "Default")
      (node (ref "U7") (pin "19") (pinfunction "CBUS3_19") (pintype "bidirectional"))
    )
    (net (code "63") (name "unconnected-(U7-~{DCD}-Pad8)") (class "Default")
      (node (ref "U7") (pin "8") (pinfunction "~{DCD}_8") (pintype "bidirectional"))
    )
    (net (code "64") (name "unconnected-(U7-~{DSR}-Pad7)") (class "Default")
      (node (ref "U7") (pin "7") (pinfunction "~{DSR}_7") (pintype "bidirectional"))
    )
    (net (code "65") (name "unconnected-(U7-~{RI}-Pad5)") (class "Default")
      (node (ref "U7") (pin "5") (pinfunction "~{RI}_5") (pintype "bidirectional"))
    )
  )
)
